# zero_cross_lm358.net
KiCad netlist of a schematic drawn in Altium Designer
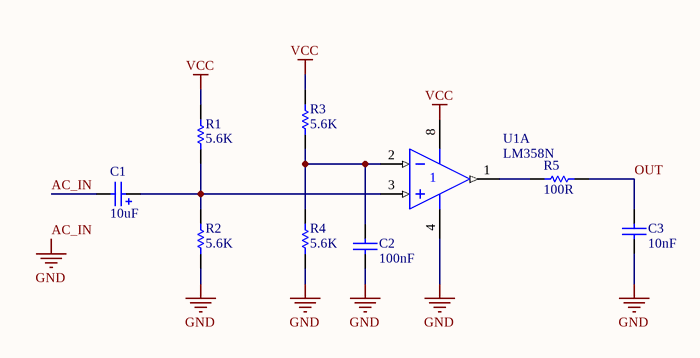
[diagram p0: zero cross lm358.SchDoc]

(export (version "E")
  (design (tool "Eeschema 10.0.6"))
  (components
    (comp (ref "C1")
      (value "10uF")
      (footprint "cap_elec_100")
      (description "Polarized Capacitor (Radial)")
      (fields (field (name "Comment") "Cap Pol") (field (name "PUBLISHER") "Altium Limited"))
      (libsource (lib "1001co") (part "Cap Pol1"))
    )
    (comp (ref "C2")
      (value "100nF")
      (footprint "cap_104")
      (description "Capacitor")
      (fields (field (name "Comment") "Cap") (field (name "PUBLISHER") "Altium Limited"))
      (libsource (lib "1001co") (part "Cap"))
    )
    (comp (ref "C3")
      (value "10nF")
      (footprint "cap_104 - 200")
      (description "Capacitor")
      (fields (field (name "Comment") "capacitor polyester") (field (name "PUBLISHER") "Altium Limited"))
      (libsource (lib "1001co") (part "Cap"))
    )
    (comp (ref "R1")
      (value "5.6K")
      (footprint "resistor_1/4_11m")
      (description "Resistor")
      (fields (field (name "Comment") "resistor") (field (name "PUBLISHER") "Altium Limited"))
      (libsource (lib "1001co") (part "Res1_1/4"))
    )
    (comp (ref "R2")
      (value "5.6K")
      (footprint "resistor_1/4_11m")
      (description "Resistor")
      (fields (field (name "Comment") "resistor") (field (name "PUBLISHER") "Altium Limited"))
      (libsource (lib "1001co") (part "Res1_1/4"))
    )
    (comp (ref "R3")
      (value "5.6K")
      (footprint "resistor_1/4_11m")
      (description "Resistor")
      (fields (field (name "Comment") "resistor") (field (name "PUBLISHER") "Altium Limited"))
      (libsource (lib "1001co") (part "Res1_1/4"))
    )
    (comp (ref "R4")
      (value "5.6K")
      (footprint "resistor_1/4_11m")
      (description "Resistor")
      (fields (field (name "Comment") "resistor") (field (name "PUBLISHER") "Altium Limited"))
      (libsource (lib "1001co") (part "Res1_1/4"))
    )
    (comp (ref "R5")
      (value "100R")
      (footprint "resistor_1/4_11m")
      (description "Resistor")
      (fields (field (name "Comment") "resistor") (field (name "PUBLISHER") "Altium Limited"))
      (libsource (lib "1001co") (part "Res1_1/4"))
    )
    (comp (ref "U1")
      (value "LM358N")
      (footprint "626-05")
      (description "Dual Low-Power Operational Amplifier")
      (fields (field (name "PUBLISHER") "Altium Limited"))
      (libsource (lib "Motorola Amplifier Operational Amplifier") (part "LM358N"))
    )
  )
  (nets
    (net (code "1") (name "/OUT") (class "Default")
      (node (ref "C3") (pin "2") (pinfunction "2_2") (pintype "passive"))
      (node (ref "R5") (pin "1") (pinfunction "1_1") (pintype "passive"))
    )
    (net (code "2") (name "GND") (class "Default")
      (node (ref "C1") (pin "2") (pinfunction "2_2") (pintype "passive"))
      (node (ref "C2") (pin "1") (pinfunction "1_1") (pintype "passive"))
      (node (ref "C3") (pin "1") (pinfunction "1_1") (pintype "passive"))
      (node (ref "R2") (pin "1") (pinfunction "1_1") (pintype "passive"))
      (node (ref "R4") (pin "1") (pinfunction "1_1") (pintype "passive"))
      (node (ref "U1") (pin "4") (pinfunction "V-_4") (pintype "power_in"))
    )
    (net (code "3") (name "Net-(U1A-IN+)") (class "Default")
      (node (ref "C1") (pin "1") (pinfunction "1_1") (pintype "passive"))
      (node (ref "R1") (pin "1") (pinfunction "1_1") (pintype "passive"))
      (node (ref "R2") (pin "2") (pinfunction "2_2") (pintype "passive"))
      (node (ref "U1") (pin "3") (pinfunction "IN+_3") (pintype "input"))
    )
    (net (code "4") (name "Net-(U1A-IN-)") (class "Default")
      (node (ref "C2") (pin "2") (pinfunction "2_2") (pintype "passive"))
      (node (ref "R3") (pin "1") (pinfunction "1_1") (pintype "passive"))
      (node (ref "R4") (pin "2") (pinfunction "2_2") (pintype "passive"))
      (node (ref "U1") (pin "2") (pinfunction "IN-_2") (pintype "input"))
    )
    (net (code "5") (name "Net-(U1A-OUT)") (class "Default")
      (node (ref "R5") (pin "2") (pinfunction "2_2") (pintype "passive"))
      (node (ref "U1") (pin "1") (pinfunction "OUT_1") (pintype "output"))
    )
    (net (code "6") (name "VCC") (class "Default")
      (node (ref "R1") (pin "2") (pinfunction "2_2") (pintype "passive"))
      (node (ref "R3") (pin "2") (pinfunction "2_2") (pintype "passive"))
      (node (ref "U1") (pin "8") (pinfunction "V+_8") (pintype "power_in"))
    )
  )
)
